# Buck.net
KiCad netlist of a schematic drawn in EasyEDA Pro
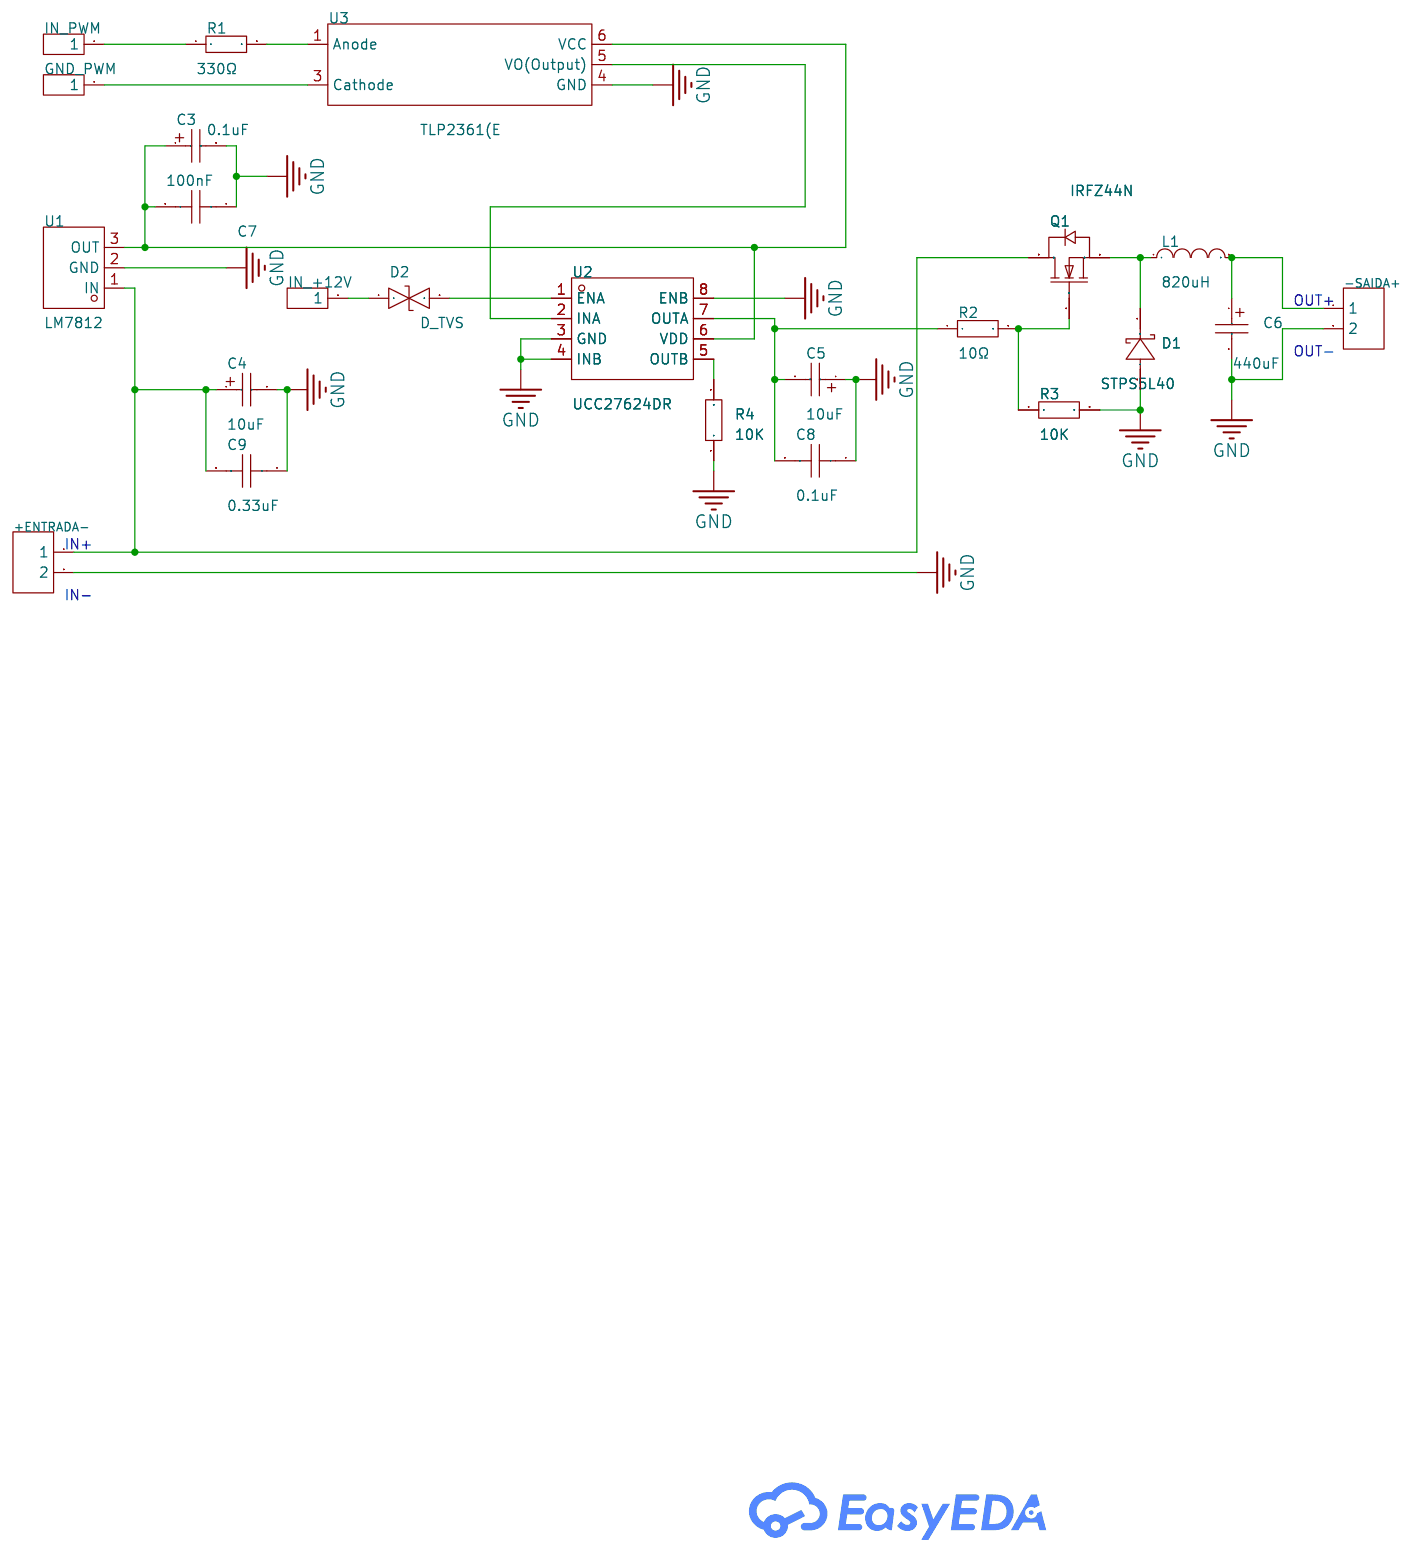
[diagram p0: schematic sheet]

(export (version "E")
  (design (tool "Eeschema 10.0.6"))
  (components
    (comp (ref "+ENTRADA-")
      (value "~")
      (footprint "easyedapro:HDR-TH_2P-P2.54-V-F")
      (libsource (lib "easyedapro") (part "Header-Female-2.54_1x2"))
    )
    (comp (ref "-SAIDA+")
      (value "~")
      (footprint "easyedapro:HDR-TH_2P-P2.54-V-F")
      (libsource (lib "easyedapro") (part "Header-Female-2.54_1x2"))
    )
    (comp (ref "C3")
      (value "0.1uF")
      (footprint "easyedapro:CAP-SMD_BD3.0-L3.3-W3.3-RD")
      (libsource (lib "easyedapro") (part "C_Ele_SMD"))
    )
    (comp (ref "C4")
      (value "10uF")
      (footprint "easyedapro:CAP-SMD_BD3.0-L3.3-W3.3-RD")
      (libsource (lib "easyedapro") (part "C_Ele_SMD"))
    )
    (comp (ref "C5")
      (value "10uF")
      (footprint "easyedapro:CAP-SMD_BD3.0-L3.3-W3.3-RD")
      (libsource (lib "easyedapro") (part "C_Ele_SMD"))
    )
    (comp (ref "C6")
      (value "440uF")
      (footprint "easyedapro:CAP-SMD_BD3.0-L3.3-W3.3-RD")
      (libsource (lib "easyedapro") (part "C_Ele_SMD"))
    )
    (comp (ref "C7")
      (value "100nF")
      (footprint "easyedapro:C0201")
      (libsource (lib "easyedapro") (part "CAP"))
    )
    (comp (ref "C8")
      (value "0.1uF")
      (footprint "easyedapro:C0201")
      (libsource (lib "easyedapro") (part "CAP"))
    )
    (comp (ref "C9")
      (value "0.33uF")
      (footprint "easyedapro:C0201")
      (libsource (lib "easyedapro") (part "CAP"))
    )
    (comp (ref "D1")
      (value "STPS5L40")
      (footprint "easyedapro:DO-201AD_BD5.3-L9.5-P13.50-D1.4-RD")
      (fields (field (name "Manufacturer") "ST(意法半导体)"))
      (libsource (lib "easyedapro") (part "STPS5L40"))
    )
    (comp (ref "D2")
      (value "D_TVS")
      (footprint "easyedapro:SMB_L4.6-W3.6-LS5.3-BI")
      (fields (field (name "Manufacturer") "Slkor(萨科微)"))
      (libsource (lib "easyedapro") (part "SMBJ36CA_C556189"))
    )
    (comp (ref "GND_PWM")
      (value "~")
      (footprint "easyedapro:HDR-TH_1P-V-M_XKB_X4611WV-01I-C28D40")
      (libsource (lib "easyedapro") (part "HDR_1x1"))
    )
    (comp (ref "IN_+12V")
      (value "~")
      (footprint "easyedapro:HDR-TH_1P-V-M_XKB_X4611WV-01I-C28D40")
      (libsource (lib "easyedapro") (part "HDR_1x1"))
    )
    (comp (ref "IN_PWM")
      (value "~")
      (footprint "easyedapro:HDR-TH_1P-V-M_XKB_X4611WV-01I-C28D40")
      (libsource (lib "easyedapro") (part "HDR_1x1"))
    )
    (comp (ref "L1")
      (value "820uH")
      (footprint "easyedapro:L0402")
      (libsource (lib "easyedapro") (part "电感"))
    )
    (comp (ref "Q1")
      (value "IRFZ44N")
      (footprint "easyedapro:TO-220-3_L9.9-W4.5-P2.54-L")
      (fields (field (name "Manufacturer") "minos(迈诺斯)"))
      (libsource (lib "easyedapro") (part "IRFZ44N"))
    )
    (comp (ref "R1")
      (value "330 Ω")
      (footprint "easyedapro:RES-TH_BD1.8-L3.2-P7.20-D0.4")
      (libsource (lib "easyedapro") (part "Res"))
    )
    (comp (ref "R2")
      (value "10 Ω")
      (footprint "easyedapro:RES-TH_BD1.8-L3.2-P7.20-D0.4")
      (libsource (lib "easyedapro") (part "Res"))
    )
    (comp (ref "R3")
      (value "10K")
      (footprint "easyedapro:RES-TH_BD1.8-L3.2-P7.20-D0.4")
      (libsource (lib "easyedapro") (part "Res"))
    )
    (comp (ref "R4")
      (value "10K")
      (footprint "easyedapro:RES-TH_BD1.8-L3.2-P7.20-D0.4")
      (libsource (lib "easyedapro") (part "Res"))
    )
    (comp (ref "U1")
      (value "LM7812")
      (footprint "easyedapro:TO-263-3_L10.1-W9.0-P5.08-LS15.2-TL")
      (fields (field (name "Manufacturer") "YONGYUTAI(永裕泰)"))
      (libsource (lib "easyedapro") (part "LM7812"))
    )
    (comp (ref "U2")
      (value "UCC27624DR")
      (footprint "easyedapro:SOIC-8_L4.9-W3.9-P1.27-LS5.9-BL")
      (fields (field (name "Manufacturer") "TI(德州仪器)"))
      (libsource (lib "easyedapro") (part "UCC27624DR"))
    )
    (comp (ref "U3")
      (value "TLP2361(E")
      (footprint "easyedapro:OPTO-SMD-5_L3.7-W4.6-P1.27-LS7.0-BR")
      (fields (field (name "Manufacturer") "TOSHIBA(东芝)"))
      (libsource (lib "easyedapro") (part "TLP2361(E"))
    )
  )
  (nets
    (net (code "1") (name "GND") (class "Default")
      (node (ref "+ENTRADA-") (pin "2") (pinfunction "2_2") (pintype "input"))
      (node (ref "-SAIDA+") (pin "2") (pinfunction "2_2") (pintype "input"))
      (node (ref "C3") (pin "2") (pinfunction "2_2") (pintype "input"))
      (node (ref "C4") (pin "2") (pinfunction "2_2") (pintype "input"))
      (node (ref "C5") (pin "1") (pinfunction "1_1") (pintype "input"))
      (node (ref "C6") (pin "2") (pinfunction "2_2") (pintype "input"))
      (node (ref "C7") (pin "1") (pinfunction "1_1") (pintype "input"))
      (node (ref "C8") (pin "1") (pinfunction "1_1") (pintype "input"))
      (node (ref "C9") (pin "1") (pinfunction "1_1") (pintype "input"))
      (node (ref "D1") (pin "2") (pinfunction "A_2") (pintype "unspecified"))
      (node (ref "R3") (pin "2") (pinfunction "2_2") (pintype "input"))
      (node (ref "R4") (pin "1") (pinfunction "1_1") (pintype "input"))
      (node (ref "U1") (pin "2") (pinfunction "GND_2") (pintype "unspecified"))
      (node (ref "U2") (pin "3") (pinfunction "GND_3") (pintype "unspecified"))
      (node (ref "U2") (pin "4") (pinfunction "INB_4") (pintype "unspecified"))
      (node (ref "U2") (pin "8") (pinfunction "ENB_8") (pintype "unspecified"))
      (node (ref "U3") (pin "4") (pinfunction "GND_4") (pintype "unspecified"))
    )
    (net (code "2") (name "Net-(-SAIDA+-Pad1)") (class "Default")
      (node (ref "-SAIDA+") (pin "1") (pinfunction "1_1") (pintype "input"))
      (node (ref "C6") (pin "1") (pinfunction "1_1") (pintype "input"))
      (node (ref "L1") (pin "2") (pinfunction "2_2") (pintype "input"))
    )
    (net (code "3") (name "Net-(D1-C)") (class "Default")
      (node (ref "D1") (pin "1") (pinfunction "C_1") (pintype "unspecified"))
      (node (ref "L1") (pin "1") (pinfunction "1_1") (pintype "input"))
      (node (ref "Q1") (pin "3") (pinfunction "S_3") (pintype "unspecified"))
    )
    (net (code "4") (name "Net-(D2-Pad1)") (class "Default")
      (node (ref "D2") (pin "1") (pinfunction "1_1") (pintype "unspecified"))
      (node (ref "IN_+12V") (pin "1") (pinfunction "1_1") (pintype "unspecified"))
    )
    (net (code "5") (name "Net-(IN_PWM-Pad1)") (class "Default")
      (node (ref "IN_PWM") (pin "1") (pinfunction "1_1") (pintype "unspecified"))
      (node (ref "R1") (pin "1") (pinfunction "1_1") (pintype "input"))
    )
    (net (code "6") (name "Net-(Q1-D)") (class "Default")
      (node (ref "+ENTRADA-") (pin "1") (pinfunction "1_1") (pintype "input"))
      (node (ref "C4") (pin "1") (pinfunction "1_1") (pintype "input"))
      (node (ref "C9") (pin "2") (pinfunction "2_2") (pintype "input"))
      (node (ref "Q1") (pin "2") (pinfunction "D_2") (pintype "unspecified"))
      (node (ref "U1") (pin "1") (pinfunction "IN_1") (pintype "unspecified"))
    )
    (net (code "7") (name "Net-(Q1-G)") (class "Default")
      (node (ref "Q1") (pin "1") (pinfunction "G_1") (pintype "unspecified"))
      (node (ref "R2") (pin "2") (pinfunction "2_2") (pintype "input"))
      (node (ref "R3") (pin "1") (pinfunction "1_1") (pintype "input"))
    )
    (net (code "8") (name "Net-(U1-OUT)") (class "Default")
      (node (ref "C3") (pin "1") (pinfunction "1_1") (pintype "input"))
      (node (ref "C7") (pin "2") (pinfunction "2_2") (pintype "input"))
      (node (ref "U1") (pin "3") (pinfunction "OUT_3") (pintype "unspecified"))
      (node (ref "U2") (pin "6") (pinfunction "VDD_6") (pintype "unspecified"))
      (node (ref "U3") (pin "6") (pinfunction "VCC_6") (pintype "unspecified"))
    )
    (net (code "9") (name "Net-(U2-ENA)") (class "Default")
      (node (ref "D2") (pin "2") (pinfunction "2_2") (pintype "unspecified"))
      (node (ref "U2") (pin "1") (pinfunction "ENA_1") (pintype "unspecified"))
    )
    (net (code "10") (name "Net-(U2-INA)") (class "Default")
      (node (ref "U2") (pin "2") (pinfunction "INA_2") (pintype "unspecified"))
      (node (ref "U3") (pin "5") (pinfunction "VO(Output)_5") (pintype "unspecified"))
    )
    (net (code "11") (name "Net-(U2-OUTA)") (class "Default")
      (node (ref "C5") (pin "2") (pinfunction "2_2") (pintype "input"))
      (node (ref "C8") (pin "2") (pinfunction "2_2") (pintype "input"))
      (node (ref "R2") (pin "1") (pinfunction "1_1") (pintype "input"))
      (node (ref "U2") (pin "7") (pinfunction "OUTA_7") (pintype "unspecified"))
    )
    (net (code "12") (name "Net-(U2-OUTB)") (class "Default")
      (node (ref "R4") (pin "2") (pinfunction "2_2") (pintype "input"))
      (node (ref "U2") (pin "5") (pinfunction "OUTB_5") (pintype "unspecified"))
    )
    (net (code "13") (name "Net-(U3-Anode)") (class "Default")
      (node (ref "R1") (pin "2") (pinfunction "2_2") (pintype "input"))
      (node (ref "U3") (pin "1") (pinfunction "Anode_1") (pintype "unspecified"))
    )
    (net (code "14") (name "Net-(U3-Cathode)") (class "Default")
      (node (ref "GND_PWM") (pin "1") (pinfunction "1_1") (pintype "unspecified"))
      (node (ref "U3") (pin "3") (pinfunction "Cathode_3") (pintype "unspecified"))
    )
  )
)
